# enkoder_moteus_schemat.net
KiCad netlist of a schematic drawn in Altium Designer
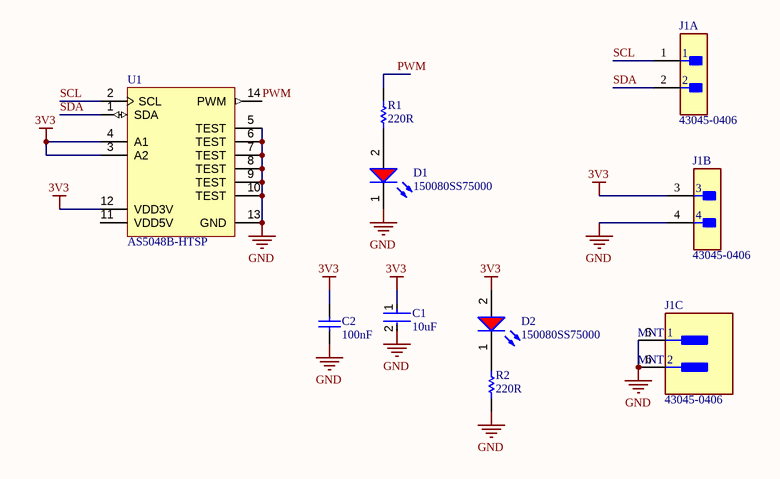
[diagram p0: enkoder_moteus_schemat.SchDoc]

(export (version "E")
  (design (tool "Eeschema 10.0.6"))
  (components
    (comp (ref "C1")
      (value "10uF")
      (footprint "FP-GRM188-0_1-e0_2_0_55-IPC_A")
      (description "Chip Multilayer Ceramic Capacitors for General Purpose, 0603, 10uF, X5R, 15%, 20%, 6.3V")
      (fields (field (name "VOLTAGE") "6.3V") (field (name "TOLERANCE") "20%"))
      (libsource (lib "Altium Content Vault") (part "02cd4be3c70576c341d710602a673aa"))
    )
    (comp (ref "C2")
      (value "100nF")
      (footprint "CAPC2013X140X50LL20T25")
      (fields
        (field (name "MANUFACTURER") "AVX Interconnect / Elco")
        (field (name "PART NUMBER") "08055F104KAT2A")
      )
      (libsource (lib "Altium Content Vault") (part "CAP"))
    )
    (comp (ref "D1")
      (value "150080SS75000")
      (footprint "WL-SMCW_0805_150080xx75000")
      (description "Led, Red, 630 Nm, 1.9 V, 30 Ma, 60 Mcd Rohs Compliant: Yes")
      (libsource (lib "Altium Content Vault") (part "LED_Red_2A-1K"))
    )
    (comp (ref "D2")
      (value "150080SS75000")
      (footprint "WL-SMCW_0805_150080xx75000")
      (description "Led, Red, 630 Nm, 1.9 V, 30 Ma, 60 Mcd Rohs Compliant: Yes")
      (libsource (lib "Altium Content Vault") (part "LED_Red_2A-1K"))
    )
    (comp (ref "J1")
      (value "43045-0406")
      (footprint "FP-43045-0406-MFG")
      (description "CONN HEADER SMD R/A 4POS 3MM")
      (libsource (lib "Altium Content Vault") (part "58585532e1459b3b5fa8464169874db"))
    )
    (comp (ref "R1")
      (value "220R")
      (footprint "RESC2013X70X40NL20T20")
      (fields (field (name "PART NUMBER") "ERJ6ENF2200V") (field (name "MANUFACTURER") "Panasonic"))
      (libsource (lib "Altium Content Vault") (part "RES"))
    )
    (comp (ref "R2")
      (value "220R")
      (footprint "RESC2013X70X40NL20T20")
      (fields (field (name "PART NUMBER") "ERJ6ENF2200V") (field (name "MANUFACTURER") "Panasonic"))
      (libsource (lib "Altium Content Vault") (part "RES"))
    )
    (comp (ref "U1")
      (value "AS5048B-HTSP")
      (footprint "AMS-TSSOP-14-5000X4400DE_L")
      (description "Magnetic Rotary Encoder 14-bit Angular Position Sensor, 3.3 or 5 V, TSSOP-14, Pb-Free, Reel")
      (fields (field (name "MANUFACTURER") "AMS"))
      (libsource (lib "Altium Content Vault") (part "AMS-AS5048B-TSSOP-14"))
    )
  )
  (nets
    (net (code "1") (name "/PWM") (class "Default")
      (node (ref "R1") (pin "2") (pinfunction "2_2") (pintype "passive"))
      (node (ref "U1") (pin "14") (pinfunction "PWM_14") (pintype "output"))
    )
    (net (code "2") (name "/SCL") (class "Default")
      (node (ref "J1") (pin "1") (pinfunction "1_1") (pintype "passive"))
      (node (ref "U1") (pin "2") (pinfunction "SCL_2") (pintype "passive"))
    )
    (net (code "3") (name "/SDA") (class "Default")
      (node (ref "J1") (pin "2") (pinfunction "2_2") (pintype "passive"))
      (node (ref "U1") (pin "1") (pinfunction "SDA_1") (pintype "bidirectional"))
    )
    (net (code "4") (name "3V3") (class "Default")
      (node (ref "C1") (pin "1") (pinfunction "1_1") (pintype "passive"))
      (node (ref "C2") (pin "2") (pinfunction "2_2") (pintype "passive"))
      (node (ref "D2") (pin "2") (pinfunction "A_2") (pintype "passive"))
      (node (ref "J1") (pin "3") (pinfunction "3_3") (pintype "passive"))
      (node (ref "U1") (pin "12") (pinfunction "VDD3V_12") (pintype "power_in"))
      (node (ref "U1") (pin "3") (pinfunction "A2_3") (pintype "passive"))
      (node (ref "U1") (pin "4") (pinfunction "A1_4") (pintype "passive"))
    )
    (net (code "5") (name "GND") (class "Default")
      (node (ref "C1") (pin "2") (pinfunction "2_2") (pintype "passive"))
      (node (ref "C2") (pin "1") (pinfunction "1_1") (pintype "passive"))
      (node (ref "D1") (pin "1") (pinfunction "K_1") (pintype "passive"))
      (node (ref "J1") (pin "4") (pinfunction "4_4") (pintype "passive"))
      (node (ref "J1") (pin "5") (pinfunction "MNT_1_5") (pintype "passive"))
      (node (ref "J1") (pin "6") (pinfunction "MNT_2_6") (pintype "passive"))
      (node (ref "R2") (pin "1") (pinfunction "1_1") (pintype "passive"))
      (node (ref "U1") (pin "10") (pinfunction "TEST_10") (pintype "passive"))
      (node (ref "U1") (pin "13") (pinfunction "GND_13") (pintype "power_in"))
      (node (ref "U1") (pin "5") (pinfunction "TEST_5") (pintype "passive"))
      (node (ref "U1") (pin "6") (pinfunction "TEST_6") (pintype "passive"))
      (node (ref "U1") (pin "7") (pinfunction "TEST_7") (pintype "passive"))
      (node (ref "U1") (pin "8") (pinfunction "TEST_8") (pintype "passive"))
      (node (ref "U1") (pin "9") (pinfunction "TEST_9") (pintype "passive"))
    )
    (net (code "6") (name "Net-(D1-A)") (class "Default")
      (node (ref "D1") (pin "2") (pinfunction "A_2") (pintype "passive"))
      (node (ref "R1") (pin "1") (pinfunction "1_1") (pintype "passive"))
    )
    (net (code "7") (name "Net-(D2-K)") (class "Default")
      (node (ref "D2") (pin "1") (pinfunction "K_1") (pintype "passive"))
      (node (ref "R2") (pin "2") (pinfunction "2_2") (pintype "passive"))
    )
    (net (code "8") (name "unconnected-(U1-VDD5V-Pad11)") (class "Default")
      (node (ref "U1") (pin "11") (pinfunction "VDD5V_11") (pintype "power_in"))
    )
  )
)
